# team_flag.net
KiCad netlist of a schematic drawn in EAGLE
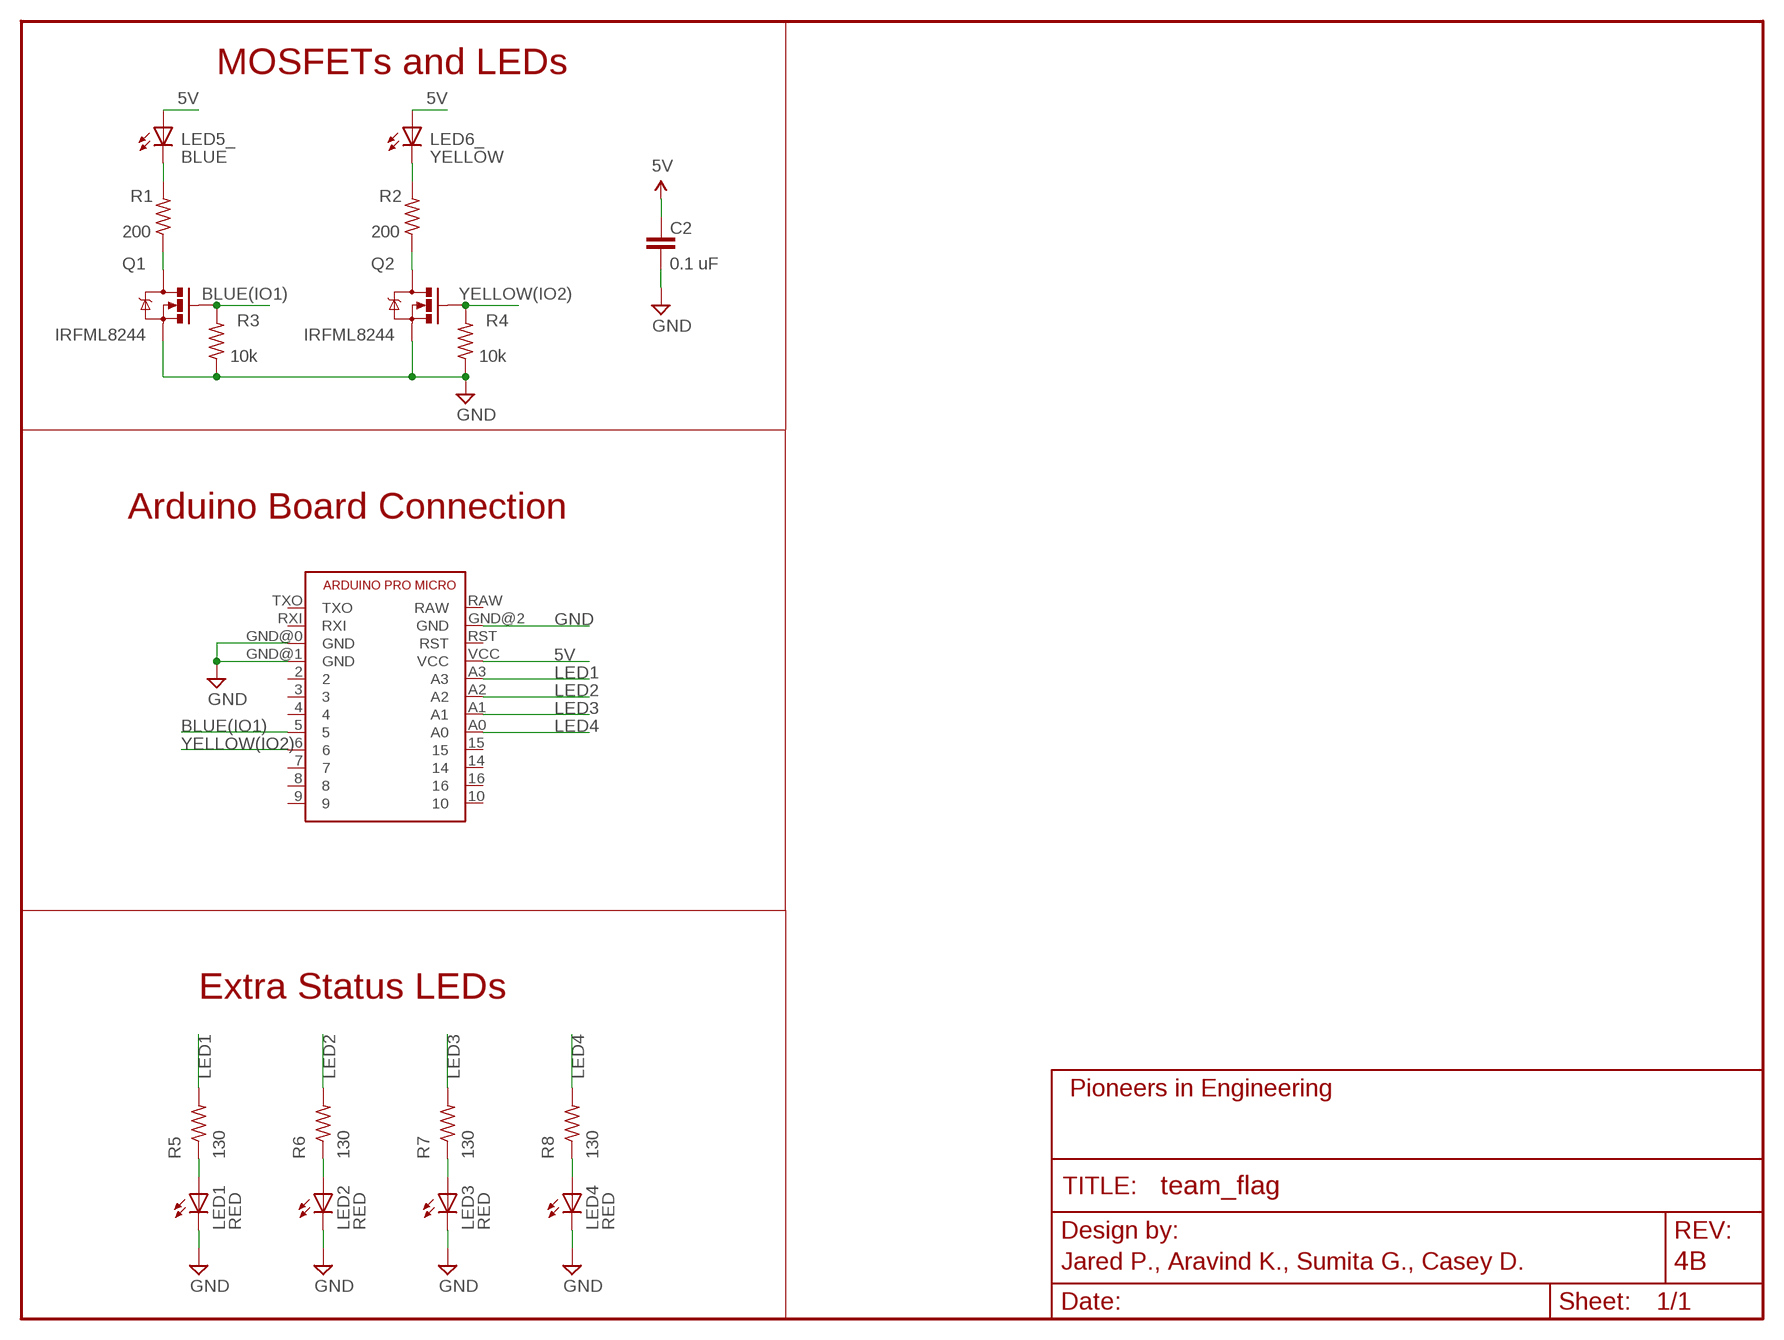
[diagram p0: schematic, sheet 1]

(export (version "E")
  (design (tool "Eeschema 10.0.6"))
  (components
    (comp (ref "C2")
      (value "0.1 uF")
      (footprint "eagle-import:0603-CAP")
      (libsource (lib "eagle-import") (part "CAP0603-CAP"))
    )
    (comp (ref "LED1")
      (value "RED")
      (footprint "eagle-import:LED-0805")
      (libsource (lib "eagle-import") (part "LED0805"))
    )
    (comp (ref "LED2")
      (value "RED")
      (footprint "eagle-import:LED-0805")
      (libsource (lib "eagle-import") (part "LED0805"))
    )
    (comp (ref "LED3")
      (value "RED")
      (footprint "eagle-import:LED-0805")
      (libsource (lib "eagle-import") (part "LED0805"))
    )
    (comp (ref "LED4")
      (value "RED")
      (footprint "eagle-import:LED-0805")
      (libsource (lib "eagle-import") (part "LED0805"))
    )
    (comp (ref "LED5_")
      (value "BLUE")
      (footprint "eagle-import:LED5MM-NOFLAT")
      (libsource (lib "eagle-import") (part "LEDLED5MM-NOFLAT"))
    )
    (comp (ref "LED6_")
      (value "YELLOW")
      (footprint "eagle-import:LED5MM-NOFLAT")
      (libsource (lib "eagle-import") (part "LEDLED5MM-NOFLAT"))
    )
    (comp (ref "Q1")
      (value "IRFML8244")
      (footprint "eagle-import:SOT23-3")
      (libsource (lib "eagle-import") (part "MOSFET-NCHANNELSMD"))
    )
    (comp (ref "Q2")
      (value "IRFML8244")
      (footprint "eagle-import:SOT23-3")
      (libsource (lib "eagle-import") (part "MOSFET-NCHANNELSMD"))
    )
    (comp (ref "R1")
      (value "200")
      (footprint "eagle-import:R0603")
      (libsource (lib "eagle-import") (part "R-US_R0603"))
    )
    (comp (ref "R2")
      (value "200")
      (footprint "eagle-import:R0603")
      (libsource (lib "eagle-import") (part "R-US_R0603"))
    )
    (comp (ref "R3")
      (value "10k")
      (footprint "eagle-import:R0603")
      (libsource (lib "eagle-import") (part "R-US_R0603"))
    )
    (comp (ref "R4")
      (value "10k")
      (footprint "eagle-import:R0603")
      (libsource (lib "eagle-import") (part "R-US_R0603"))
    )
    (comp (ref "R5")
      (value "130")
      (footprint "eagle-import:R0603")
      (libsource (lib "eagle-import") (part "R-US_R0603"))
    )
    (comp (ref "R6")
      (value "130")
      (footprint "eagle-import:R0603")
      (libsource (lib "eagle-import") (part "R-US_R0603"))
    )
    (comp (ref "R7")
      (value "130")
      (footprint "eagle-import:R0603")
      (libsource (lib "eagle-import") (part "R-US_R0603"))
    )
    (comp (ref "R8")
      (value "130")
      (footprint "eagle-import:R0603")
      (libsource (lib "eagle-import") (part "R-US_R0603"))
    )
    (comp (ref "U$3")
      (value "ARDUINO_PRO_MICRO")
      (footprint "eagle-import:ARDUINO_PRO_MICRO")
      (libsource (lib "eagle-import") (part "ARDUINO_PRO_MICRO"))
    )
  )
  (nets
    (net (code "1") (name "/BLUE(IO1)") (class "Default")
      (node (ref "Q1") (pin "1") (pinfunction "G_1") (pintype "passive"))
      (node (ref "R3") (pin "2") (pinfunction "2_2") (pintype "passive"))
      (node (ref "U$3") (pin "5") (pinfunction "5_5") (pintype "bidirectional"))
    )
    (net (code "2") (name "/LED1") (class "Default")
      (node (ref "R5") (pin "2") (pinfunction "2_2") (pintype "passive"))
      (node (ref "U$3") (pin "A3") (pinfunction "A3_A3") (pintype "bidirectional"))
    )
    (net (code "3") (name "/LED2") (class "Default")
      (node (ref "R6") (pin "2") (pinfunction "2_2") (pintype "passive"))
      (node (ref "U$3") (pin "A2") (pinfunction "A2_A2") (pintype "bidirectional"))
    )
    (net (code "4") (name "/LED3") (class "Default")
      (node (ref "R7") (pin "2") (pinfunction "2_2") (pintype "passive"))
      (node (ref "U$3") (pin "A1") (pinfunction "A1_A1") (pintype "bidirectional"))
    )
    (net (code "5") (name "/LED4") (class "Default")
      (node (ref "R8") (pin "2") (pinfunction "2_2") (pintype "passive"))
      (node (ref "U$3") (pin "A0") (pinfunction "A0_A0") (pintype "bidirectional"))
    )
    (net (code "6") (name "/YELLOW(IO2)") (class "Default")
      (node (ref "Q2") (pin "1") (pinfunction "G_1") (pintype "passive"))
      (node (ref "R4") (pin "2") (pinfunction "2_2") (pintype "passive"))
      (node (ref "U$3") (pin "6") (pinfunction "6_6") (pintype "bidirectional"))
    )
    (net (code "7") (name "5V") (class "Default")
      (node (ref "C2") (pin "1") (pinfunction "1_1") (pintype "passive"))
      (node (ref "LED5_") (pin "A") (pinfunction "A_A") (pintype "passive"))
      (node (ref "LED6_") (pin "A") (pinfunction "A_A") (pintype "passive"))
      (node (ref "U$3") (pin "VCC") (pinfunction "VCC_VCC") (pintype "bidirectional"))
    )
    (net (code "8") (name "GND") (class "Default")
      (node (ref "C2") (pin "2") (pinfunction "2_2") (pintype "passive"))
      (node (ref "LED1") (pin "C") (pinfunction "C_C") (pintype "passive"))
      (node (ref "LED2") (pin "C") (pinfunction "C_C") (pintype "passive"))
      (node (ref "LED3") (pin "C") (pinfunction "C_C") (pintype "passive"))
      (node (ref "LED4") (pin "C") (pinfunction "C_C") (pintype "passive"))
      (node (ref "Q1") (pin "2") (pinfunction "S_2") (pintype "passive"))
      (node (ref "Q2") (pin "2") (pinfunction "S_2") (pintype "passive"))
      (node (ref "R3") (pin "1") (pinfunction "1_1") (pintype "passive"))
      (node (ref "R4") (pin "1") (pinfunction "1_1") (pintype "passive"))
      (node (ref "U$3") (pin "GND@0") (pinfunction "GND_GND@0") (pintype "bidirectional"))
      (node (ref "U$3") (pin "GND@1") (pinfunction "GND_GND@1") (pintype "bidirectional"))
      (node (ref "U$3") (pin "GND@2") (pinfunction "GND_GND@2") (pintype "bidirectional"))
    )
    (net (code "9") (name "Net-(LED1-PadA)") (class "Default")
      (node (ref "LED1") (pin "A") (pinfunction "A_A") (pintype "passive"))
      (node (ref "R5") (pin "1") (pinfunction "1_1") (pintype "passive"))
    )
    (net (code "10") (name "Net-(LED2-PadA)") (class "Default")
      (node (ref "LED2") (pin "A") (pinfunction "A_A") (pintype "passive"))
      (node (ref "R6") (pin "1") (pinfunction "1_1") (pintype "passive"))
    )
    (net (code "11") (name "Net-(LED3-PadA)") (class "Default")
      (node (ref "LED3") (pin "A") (pinfunction "A_A") (pintype "passive"))
      (node (ref "R7") (pin "1") (pinfunction "1_1") (pintype "passive"))
    )
    (net (code "12") (name "Net-(LED4-PadA)") (class "Default")
      (node (ref "LED4") (pin "A") (pinfunction "A_A") (pintype "passive"))
      (node (ref "R8") (pin "1") (pinfunction "1_1") (pintype "passive"))
    )
    (net (code "13") (name "Net-(LED5_-C)") (class "Default")
      (node (ref "LED5_") (pin "K") (pinfunction "C_K") (pintype "passive"))
      (node (ref "R1") (pin "2") (pinfunction "2_2") (pintype "passive"))
    )
    (net (code "14") (name "Net-(LED6_-C)") (class "Default")
      (node (ref "LED6_") (pin "K") (pinfunction "C_K") (pintype "passive"))
      (node (ref "R2") (pin "2") (pinfunction "2_2") (pintype "passive"))
    )
    (net (code "15") (name "Net-(Q1-D)") (class "Default")
      (node (ref "Q1") (pin "3") (pinfunction "D_3") (pintype "passive"))
      (node (ref "R1") (pin "1") (pinfunction "1_1") (pintype "passive"))
    )
    (net (code "16") (name "Net-(Q2-D)") (class "Default")
      (node (ref "Q2") (pin "3") (pinfunction "D_3") (pintype "passive"))
      (node (ref "R2") (pin "1") (pinfunction "1_1") (pintype "passive"))
    )
    (net (code "17") (name "unconnected-(U$3-Pad2)") (class "Default")
      (node (ref "U$3") (pin "2") (pinfunction "2_2") (pintype "bidirectional"))
    )
    (net (code "18") (name "unconnected-(U$3-Pad3)") (class "Default")
      (node (ref "U$3") (pin "3") (pinfunction "3_3") (pintype "bidirectional"))
    )
    (net (code "19") (name "unconnected-(U$3-Pad4)") (class "Default")
      (node (ref "U$3") (pin "4") (pinfunction "4_4") (pintype "bidirectional"))
    )
    (net (code "20") (name "unconnected-(U$3-Pad7)") (class "Default")
      (node (ref "U$3") (pin "7") (pinfunction "7_7") (pintype "bidirectional"))
    )
    (net (code "21") (name "unconnected-(U$3-Pad8)") (class "Default")
      (node (ref "U$3") (pin "8") (pinfunction "8_8") (pintype "bidirectional"))
    )
    (net (code "22") (name "unconnected-(U$3-Pad9)") (class "Default")
      (node (ref "U$3") (pin "9") (pinfunction "9_9") (pintype "bidirectional"))
    )
    (net (code "23") (name "unconnected-(U$3-Pad10)") (class "Default")
      (node (ref "U$3") (pin "10") (pinfunction "10_10") (pintype "bidirectional"))
    )
    (net (code "24") (name "unconnected-(U$3-Pad14)") (class "Default")
      (node (ref "U$3") (pin "14") (pinfunction "14_14") (pintype "bidirectional"))
    )
    (net (code "25") (name "unconnected-(U$3-Pad15)") (class "Default")
      (node (ref "U$3") (pin "15") (pinfunction "15_15") (pintype "bidirectional"))
    )
    (net (code "26") (name "unconnected-(U$3-Pad16)") (class "Default")
      (node (ref "U$3") (pin "16") (pinfunction "16_16") (pintype "bidirectional"))
    )
    (net (code "27") (name "unconnected-(U$3-PadRAW)") (class "Default")
      (node (ref "U$3") (pin "RAW") (pinfunction "RAW_RAW") (pintype "bidirectional"))
    )
    (net (code "28") (name "unconnected-(U$3-PadRST)") (class "Default")
      (node (ref "U$3") (pin "RST") (pinfunction "RST_RST") (pintype "bidirectional"))
    )
    (net (code "29") (name "unconnected-(U$3-PadRXI)") (class "Default")
      (node (ref "U$3") (pin "RXI") (pinfunction "RXI_RXI") (pintype "bidirectional"))
    )
    (net (code "30") (name "unconnected-(U$3-PadTXO)") (class "Default")
      (node (ref "U$3") (pin "TXO") (pinfunction "TXO_TXO") (pintype "bidirectional"))
    )
  )
)
